# mightIO.net
KiCad netlist of a schematic drawn in EAGLE
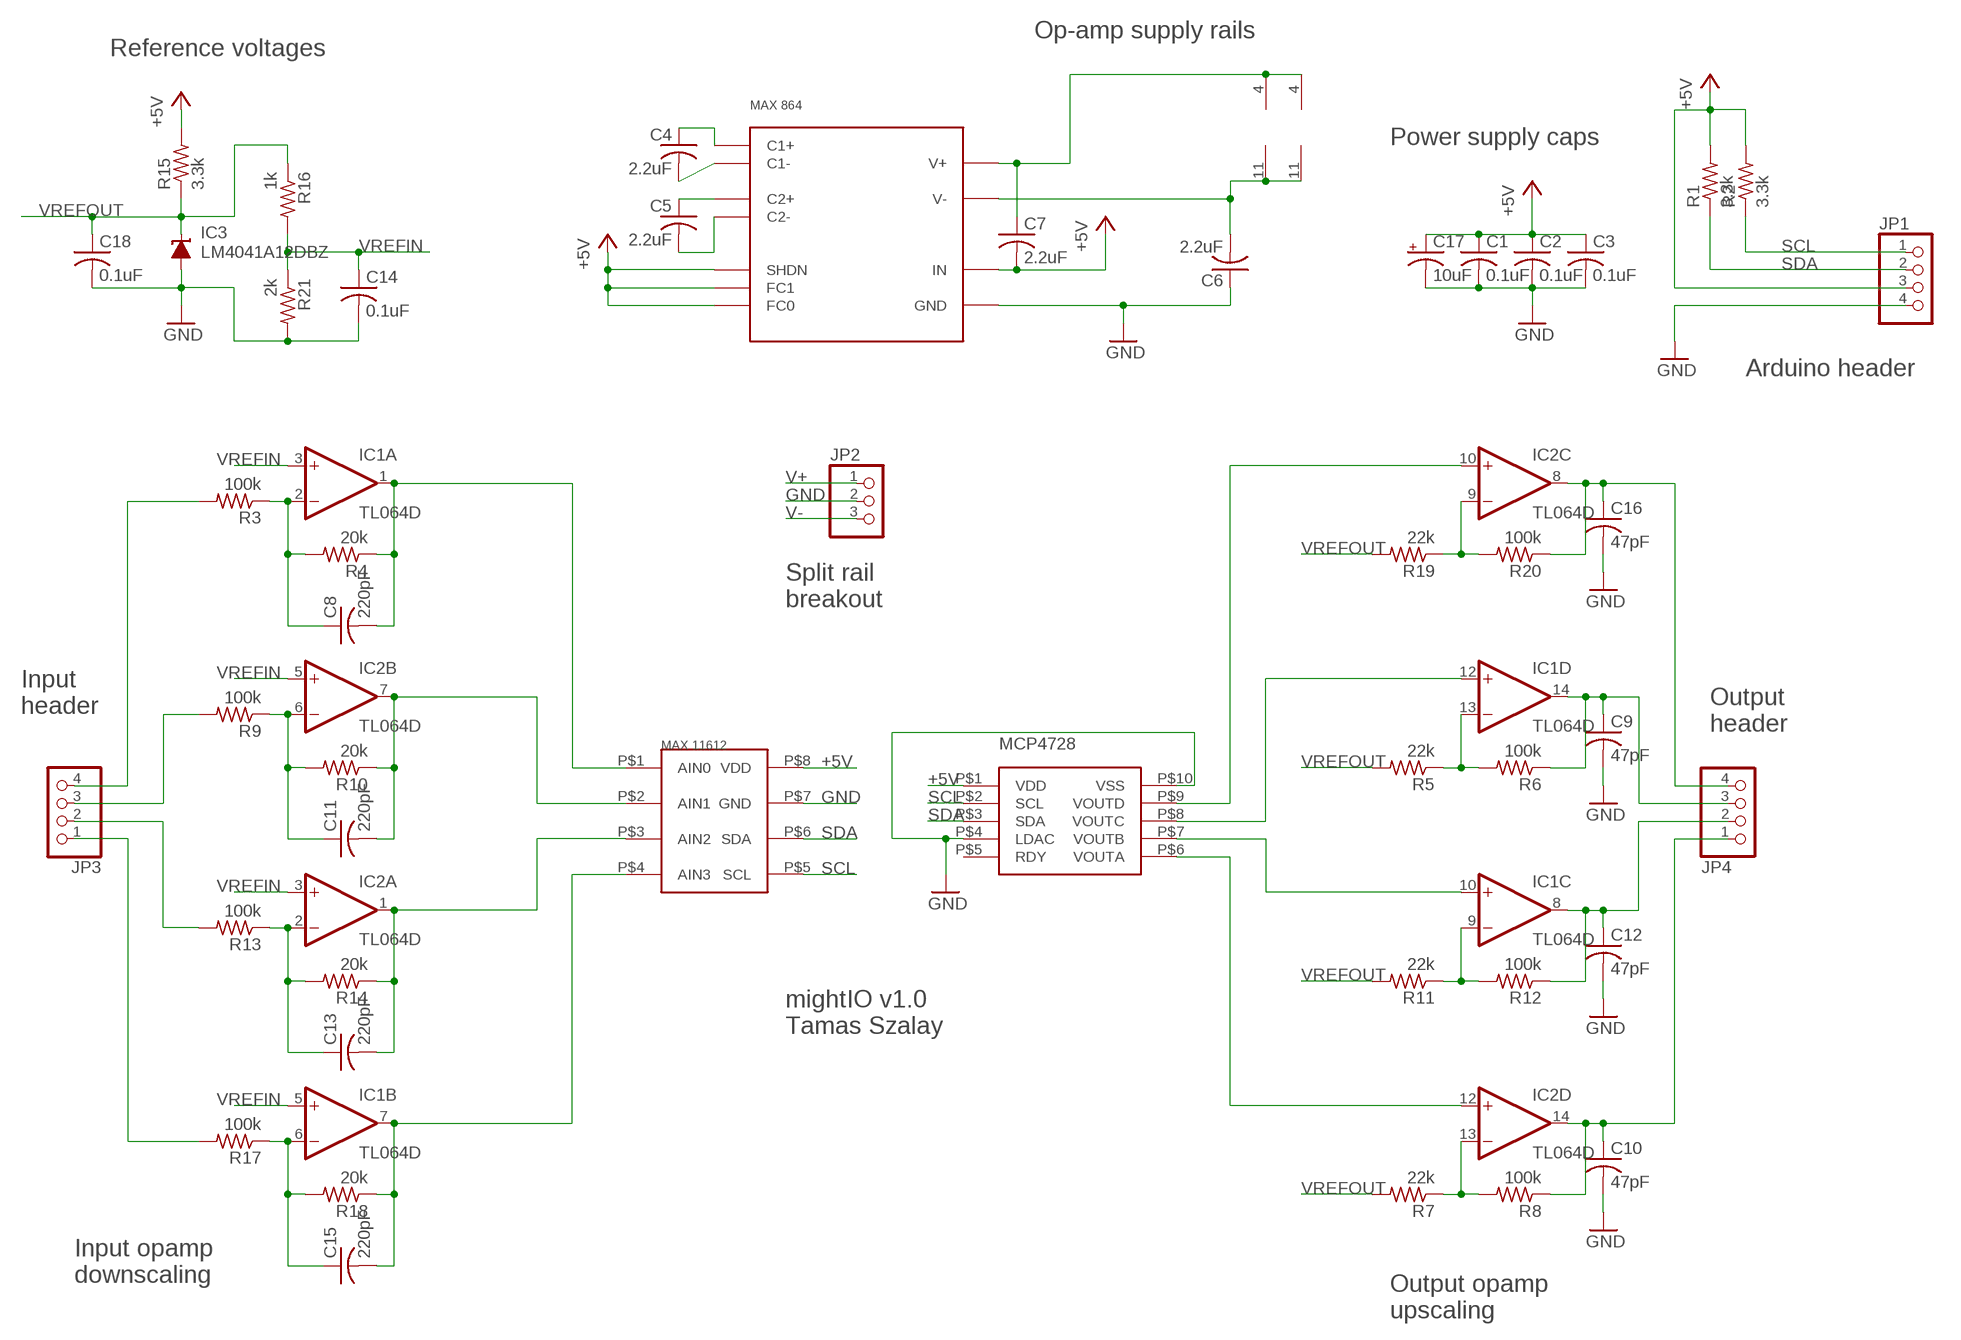
[diagram p0: schematic, sheet 1]

(export (version "E")
  (design (tool "Eeschema 10.0.6"))
  (components
    (comp (ref "C1")
      (value "0.1uF")
      (footprint "eagle-import:C0603")
      (libsource (lib "eagle-import") (part "C-USC0603"))
    )
    (comp (ref "C2")
      (value "0.1uF")
      (footprint "eagle-import:C0603")
      (libsource (lib "eagle-import") (part "C-USC0603"))
    )
    (comp (ref "C3")
      (value "0.1uF")
      (footprint "eagle-import:C0603")
      (libsource (lib "eagle-import") (part "C-USC0603"))
    )
    (comp (ref "C4")
      (value "2.2uF")
      (footprint "eagle-import:C0603")
      (libsource (lib "eagle-import") (part "C-USC0603"))
    )
    (comp (ref "C5")
      (value "2.2uF")
      (footprint "eagle-import:C0603")
      (libsource (lib "eagle-import") (part "C-USC0603"))
    )
    (comp (ref "C6")
      (value "2.2uF")
      (footprint "eagle-import:C0603")
      (libsource (lib "eagle-import") (part "C-USC0603"))
    )
    (comp (ref "C7")
      (value "2.2uF")
      (footprint "eagle-import:C0603")
      (libsource (lib "eagle-import") (part "C-USC0603"))
    )
    (comp (ref "C8")
      (value "220pF")
      (footprint "eagle-import:C0603")
      (libsource (lib "eagle-import") (part "C-USC0603"))
    )
    (comp (ref "C9")
      (value "47pF")
      (footprint "eagle-import:C0603")
      (libsource (lib "eagle-import") (part "C-USC0603"))
    )
    (comp (ref "C10")
      (value "47pF")
      (footprint "eagle-import:C0603")
      (libsource (lib "eagle-import") (part "C-USC0603"))
    )
    (comp (ref "C11")
      (value "220pF")
      (footprint "eagle-import:C0603")
      (libsource (lib "eagle-import") (part "C-USC0603"))
    )
    (comp (ref "C12")
      (value "47pF")
      (footprint "eagle-import:C0603")
      (libsource (lib "eagle-import") (part "C-USC0603"))
    )
    (comp (ref "C13")
      (value "220pF")
      (footprint "eagle-import:C0603")
      (libsource (lib "eagle-import") (part "C-USC0603"))
    )
    (comp (ref "C14")
      (value "0.1uF")
      (footprint "eagle-import:C0603")
      (libsource (lib "eagle-import") (part "C-USC0603"))
    )
    (comp (ref "C15")
      (value "220pF")
      (footprint "eagle-import:C0603")
      (libsource (lib "eagle-import") (part "C-USC0603"))
    )
    (comp (ref "C16")
      (value "47pF")
      (footprint "eagle-import:C0603")
      (libsource (lib "eagle-import") (part "C-USC0603"))
    )
    (comp (ref "C17")
      (value "10uF")
      (footprint "eagle-import:E2,5-6")
      (libsource (lib "eagle-import") (part "CPOL-USE2.5-6"))
    )
    (comp (ref "C18")
      (value "0.1uF")
      (footprint "eagle-import:C0603")
      (libsource (lib "eagle-import") (part "C-USC0603"))
    )
    (comp (ref "IC1")
      (value "TL064D")
      (footprint "eagle-import:SO14")
      (libsource (lib "eagle-import") (part "TL064D"))
    )
    (comp (ref "IC2")
      (value "TL064D")
      (footprint "eagle-import:SO14")
      (libsource (lib "eagle-import") (part "TL064D"))
    )
    (comp (ref "IC3")
      (value "LM4041A12DBZ")
      (footprint "eagle-import:DBZ_R-PDSO-G3")
      (fields (field (name "MPN") "LM4041A12IDBZR"))
      (libsource (lib "eagle-import") (part "LM4041DBZA12"))
    )
    (comp (ref "JP1")
      (value "PINHD-1X4")
      (footprint "eagle-import:1X04")
      (libsource (lib "eagle-import") (part "PINHD-1X4"))
    )
    (comp (ref "JP2")
      (value "PINHD-1X3")
      (footprint "eagle-import:1X03")
      (libsource (lib "eagle-import") (part "PINHD-1X3"))
    )
    (comp (ref "JP3")
      (value "PINHD-1X4")
      (footprint "eagle-import:1X04")
      (libsource (lib "eagle-import") (part "PINHD-1X4"))
    )
    (comp (ref "JP4")
      (value "PINHD-1X4")
      (footprint "eagle-import:1X04")
      (libsource (lib "eagle-import") (part "PINHD-1X4"))
    )
    (comp (ref "R1")
      (value "3.3k")
      (footprint "eagle-import:R0603")
      (libsource (lib "eagle-import") (part "R-US_R0603"))
    )
    (comp (ref "R2")
      (value "3.3k")
      (footprint "eagle-import:R0603")
      (libsource (lib "eagle-import") (part "R-US_R0603"))
    )
    (comp (ref "R3")
      (value "100k")
      (footprint "eagle-import:R0603")
      (libsource (lib "eagle-import") (part "R-US_R0603"))
    )
    (comp (ref "R4")
      (value "20k")
      (footprint "eagle-import:R0603")
      (libsource (lib "eagle-import") (part "R-US_R0603"))
    )
    (comp (ref "R5")
      (value "22k")
      (footprint "eagle-import:R0603")
      (libsource (lib "eagle-import") (part "R-US_R0603"))
    )
    (comp (ref "R6")
      (value "100k")
      (footprint "eagle-import:R0603")
      (libsource (lib "eagle-import") (part "R-US_R0603"))
    )
    (comp (ref "R7")
      (value "22k")
      (footprint "eagle-import:R0603")
      (libsource (lib "eagle-import") (part "R-US_R0603"))
    )
    (comp (ref "R8")
      (value "100k")
      (footprint "eagle-import:R0603")
      (libsource (lib "eagle-import") (part "R-US_R0603"))
    )
    (comp (ref "R9")
      (value "100k")
      (footprint "eagle-import:R0603")
      (libsource (lib "eagle-import") (part "R-US_R0603"))
    )
    (comp (ref "R10")
      (value "20k")
      (footprint "eagle-import:R0603")
      (libsource (lib "eagle-import") (part "R-US_R0603"))
    )
    (comp (ref "R11")
      (value "22k")
      (footprint "eagle-import:R0603")
      (libsource (lib "eagle-import") (part "R-US_R0603"))
    )
    (comp (ref "R12")
      (value "100k")
      (footprint "eagle-import:R0603")
      (libsource (lib "eagle-import") (part "R-US_R0603"))
    )
    (comp (ref "R13")
      (value "100k")
      (footprint "eagle-import:R0603")
      (libsource (lib "eagle-import") (part "R-US_R0603"))
    )
    (comp (ref "R14")
      (value "20k")
      (footprint "eagle-import:R0603")
      (libsource (lib "eagle-import") (part "R-US_R0603"))
    )
    (comp (ref "R15")
      (value "3.3k")
      (footprint "eagle-import:R0603")
      (libsource (lib "eagle-import") (part "R-US_R0603"))
    )
    (comp (ref "R16")
      (value "1k")
      (footprint "eagle-import:R0603")
      (libsource (lib "eagle-import") (part "R-US_R0603"))
    )
    (comp (ref "R17")
      (value "100k")
      (footprint "eagle-import:R0603")
      (libsource (lib "eagle-import") (part "R-US_R0603"))
    )
    (comp (ref "R18")
      (value "20k")
      (footprint "eagle-import:R0603")
      (libsource (lib "eagle-import") (part "R-US_R0603"))
    )
    (comp (ref "R19")
      (value "22k")
      (footprint "eagle-import:R0603")
      (libsource (lib "eagle-import") (part "R-US_R0603"))
    )
    (comp (ref "R20")
      (value "100k")
      (footprint "eagle-import:R0603")
      (libsource (lib "eagle-import") (part "R-US_R0603"))
    )
    (comp (ref "R21")
      (value "2k")
      (footprint "eagle-import:R0603")
      (libsource (lib "eagle-import") (part "R-US_R0603"))
    )
    (comp (ref "U$1")
      (value "MAX864")
      (footprint "eagle-import:MAX864")
      (libsource (lib "eagle-import") (part "MAX864"))
    )
    (comp (ref "U$2")
      (value "MCP4728")
      (footprint "eagle-import:MCP4728")
      (libsource (lib "eagle-import") (part "MCP4728"))
    )
    (comp (ref "U1")
      (value "MAX11612")
      (footprint "eagle-import:MAX11612")
      (libsource (lib "eagle-import") (part "MAX11612"))
    )
  )
  (nets
    (net (code "1") (name "+5V") (class "Default")
      (node (ref "C1") (pin "1") (pinfunction "1_1") (pintype "passive"))
      (node (ref "C17") (pin "+") (pinfunction "+_+") (pintype "passive"))
      (node (ref "C2") (pin "1") (pinfunction "1_1") (pintype "passive"))
      (node (ref "C3") (pin "1") (pinfunction "1_1") (pintype "passive"))
      (node (ref "C7") (pin "2") (pinfunction "2_2") (pintype "passive"))
      (node (ref "JP1") (pin "3") (pinfunction "3_3") (pintype "passive"))
      (node (ref "R1") (pin "2") (pinfunction "2_2") (pintype "passive"))
      (node (ref "R15") (pin "2") (pinfunction "2_2") (pintype "passive"))
      (node (ref "R2") (pin "2") (pinfunction "2_2") (pintype "passive"))
      (node (ref "U$1") (pin "P$12") (pinfunction "IN_P$12") (pintype "bidirectional"))
      (node (ref "U$1") (pin "P$6") (pinfunction "SHDN_P$6") (pintype "bidirectional"))
      (node (ref "U$1") (pin "P$7") (pinfunction "FC1_P$7") (pintype "bidirectional"))
      (node (ref "U$1") (pin "P$8") (pinfunction "FC0_P$8") (pintype "bidirectional"))
      (node (ref "U$2") (pin "P$1") (pinfunction "VDD_P$1") (pintype "bidirectional"))
      (node (ref "U1") (pin "P$8") (pinfunction "VDD_P$8") (pintype "bidirectional"))
    )
    (net (code "2") (name "/SCL") (class "Default")
      (node (ref "JP1") (pin "1") (pinfunction "1_1") (pintype "passive"))
      (node (ref "R2") (pin "1") (pinfunction "1_1") (pintype "passive"))
      (node (ref "U$2") (pin "P$2") (pinfunction "SCL_P$2") (pintype "bidirectional"))
      (node (ref "U1") (pin "P$5") (pinfunction "SCL_P$5") (pintype "bidirectional"))
    )
    (net (code "3") (name "/SDA") (class "Default")
      (node (ref "JP1") (pin "2") (pinfunction "2_2") (pintype "passive"))
      (node (ref "R1") (pin "1") (pinfunction "1_1") (pintype "passive"))
      (node (ref "U$2") (pin "P$3") (pinfunction "SDA_P$3") (pintype "bidirectional"))
      (node (ref "U1") (pin "P$6") (pinfunction "SDA_P$6") (pintype "bidirectional"))
    )
    (net (code "4") (name "/V+") (class "Default")
      (node (ref "C7") (pin "1") (pinfunction "1_1") (pintype "passive"))
      (node (ref "IC1") (pin "4") (pinfunction "V+_4") (pintype "power_in"))
      (node (ref "IC2") (pin "4") (pinfunction "V+_4") (pintype "power_in"))
      (node (ref "JP2") (pin "1") (pinfunction "1_1") (pintype "passive"))
      (node (ref "U$1") (pin "P$15") (pinfunction "V+_P$15") (pintype "bidirectional"))
    )
    (net (code "5") (name "/V-") (class "Default")
      (node (ref "C6") (pin "2") (pinfunction "2_2") (pintype "passive"))
      (node (ref "IC1") (pin "11") (pinfunction "V-_11") (pintype "power_in"))
      (node (ref "IC2") (pin "11") (pinfunction "V-_11") (pintype "power_in"))
      (node (ref "JP2") (pin "3") (pinfunction "3_3") (pintype "passive"))
      (node (ref "U$1") (pin "P$5") (pinfunction "V-_P$5") (pintype "bidirectional"))
    )
    (net (code "6") (name "/VREFIN") (class "Default")
      (node (ref "C14") (pin "1") (pinfunction "1_1") (pintype "passive"))
      (node (ref "IC1") (pin "3") (pinfunction "+IN_3") (pintype "input"))
      (node (ref "IC1") (pin "5") (pinfunction "+IN_5") (pintype "input"))
      (node (ref "IC2") (pin "3") (pinfunction "+IN_3") (pintype "input"))
      (node (ref "IC2") (pin "5") (pinfunction "+IN_5") (pintype "input"))
      (node (ref "R16") (pin "2") (pinfunction "2_2") (pintype "passive"))
      (node (ref "R21") (pin "1") (pinfunction "1_1") (pintype "passive"))
    )
    (net (code "7") (name "/VREFOUT") (class "Default")
      (node (ref "C18") (pin "1") (pinfunction "1_1") (pintype "passive"))
      (node (ref "IC3") (pin "1") (pinfunction "C_1") (pintype "passive"))
      (node (ref "R11") (pin "2") (pinfunction "2_2") (pintype "passive"))
      (node (ref "R15") (pin "1") (pinfunction "1_1") (pintype "passive"))
      (node (ref "R16") (pin "1") (pinfunction "1_1") (pintype "passive"))
      (node (ref "R19") (pin "2") (pinfunction "2_2") (pintype "passive"))
      (node (ref "R5") (pin "2") (pinfunction "2_2") (pintype "passive"))
      (node (ref "R7") (pin "2") (pinfunction "2_2") (pintype "passive"))
    )
    (net (code "8") (name "GND") (class "Default")
      (node (ref "C1") (pin "2") (pinfunction "2_2") (pintype "passive"))
      (node (ref "C10") (pin "2") (pinfunction "2_2") (pintype "passive"))
      (node (ref "C12") (pin "2") (pinfunction "2_2") (pintype "passive"))
      (node (ref "C14") (pin "2") (pinfunction "2_2") (pintype "passive"))
      (node (ref "C16") (pin "2") (pinfunction "2_2") (pintype "passive"))
      (node (ref "C17") (pin "-") (pinfunction "-_-") (pintype "passive"))
      (node (ref "C18") (pin "2") (pinfunction "2_2") (pintype "passive"))
      (node (ref "C2") (pin "2") (pinfunction "2_2") (pintype "passive"))
      (node (ref "C3") (pin "2") (pinfunction "2_2") (pintype "passive"))
      (node (ref "C6") (pin "1") (pinfunction "1_1") (pintype "passive"))
      (node (ref "C9") (pin "2") (pinfunction "2_2") (pintype "passive"))
      (node (ref "IC3") (pin "2") (pinfunction "A_2") (pintype "passive"))
      (node (ref "JP1") (pin "4") (pinfunction "4_4") (pintype "passive"))
      (node (ref "JP2") (pin "2") (pinfunction "2_2") (pintype "passive"))
      (node (ref "R21") (pin "2") (pinfunction "2_2") (pintype "passive"))
      (node (ref "U$1") (pin "P$11") (pinfunction "GND_P$11") (pintype "bidirectional"))
      (node (ref "U$1") (pin "P$3") (pinfunction "GND_P$3") (pintype "bidirectional"))
      (node (ref "U$2") (pin "P$10") (pinfunction "VSS_P$10") (pintype "bidirectional"))
      (node (ref "U$2") (pin "P$4") (pinfunction "LDAC_P$4") (pintype "bidirectional"))
      (node (ref "U1") (pin "P$7") (pinfunction "GND_P$7") (pintype "bidirectional"))
    )
    (net (code "9") (name "Net-(IC1A--IN)") (class "Default")
      (node (ref "C8") (pin "1") (pinfunction "1_1") (pintype "passive"))
      (node (ref "IC1") (pin "2") (pinfunction "-IN_2") (pintype "input"))
      (node (ref "R3") (pin "1") (pinfunction "1_1") (pintype "passive"))
      (node (ref "R4") (pin "2") (pinfunction "2_2") (pintype "passive"))
    )
    (net (code "10") (name "Net-(IC1A-OUT)") (class "Default")
      (node (ref "C8") (pin "2") (pinfunction "2_2") (pintype "passive"))
      (node (ref "IC1") (pin "1") (pinfunction "OUT_1") (pintype "output"))
      (node (ref "R4") (pin "1") (pinfunction "1_1") (pintype "passive"))
      (node (ref "U1") (pin "P$1") (pinfunction "AIN0_P$1") (pintype "bidirectional"))
    )
    (net (code "11") (name "Net-(IC1B--IN)") (class "Default")
      (node (ref "C15") (pin "1") (pinfunction "1_1") (pintype "passive"))
      (node (ref "IC1") (pin "6") (pinfunction "-IN_6") (pintype "input"))
      (node (ref "R17") (pin "1") (pinfunction "1_1") (pintype "passive"))
      (node (ref "R18") (pin "2") (pinfunction "2_2") (pintype "passive"))
    )
    (net (code "12") (name "Net-(IC1B-OUT)") (class "Default")
      (node (ref "C15") (pin "2") (pinfunction "2_2") (pintype "passive"))
      (node (ref "IC1") (pin "7") (pinfunction "OUT_7") (pintype "output"))
      (node (ref "R18") (pin "1") (pinfunction "1_1") (pintype "passive"))
      (node (ref "U1") (pin "P$4") (pinfunction "AIN3_P$4") (pintype "bidirectional"))
    )
    (net (code "13") (name "Net-(IC1C-+IN)") (class "Default")
      (node (ref "IC1") (pin "10") (pinfunction "+IN_10") (pintype "input"))
      (node (ref "U$2") (pin "P$7") (pinfunction "VOUTB_P$7") (pintype "bidirectional"))
    )
    (net (code "14") (name "Net-(IC1C--IN)") (class "Default")
      (node (ref "IC1") (pin "9") (pinfunction "-IN_9") (pintype "input"))
      (node (ref "R11") (pin "1") (pinfunction "1_1") (pintype "passive"))
      (node (ref "R12") (pin "2") (pinfunction "2_2") (pintype "passive"))
    )
    (net (code "15") (name "Net-(IC1C-OUT)") (class "Default")
      (node (ref "C12") (pin "1") (pinfunction "1_1") (pintype "passive"))
      (node (ref "IC1") (pin "8") (pinfunction "OUT_8") (pintype "output"))
      (node (ref "JP4") (pin "2") (pinfunction "2_2") (pintype "passive"))
      (node (ref "R12") (pin "1") (pinfunction "1_1") (pintype "passive"))
    )
    (net (code "16") (name "Net-(IC1D-+IN)") (class "Default")
      (node (ref "IC1") (pin "12") (pinfunction "+IN_12") (pintype "input"))
      (node (ref "U$2") (pin "P$8") (pinfunction "VOUTC_P$8") (pintype "bidirectional"))
    )
    (net (code "17") (name "Net-(IC1D--IN)") (class "Default")
      (node (ref "IC1") (pin "13") (pinfunction "-IN_13") (pintype "input"))
      (node (ref "R5") (pin "1") (pinfunction "1_1") (pintype "passive"))
      (node (ref "R6") (pin "2") (pinfunction "2_2") (pintype "passive"))
    )
    (net (code "18") (name "Net-(IC1D-OUT)") (class "Default")
      (node (ref "C9") (pin "1") (pinfunction "1_1") (pintype "passive"))
      (node (ref "IC1") (pin "14") (pinfunction "OUT_14") (pintype "output"))
      (node (ref "JP4") (pin "3") (pinfunction "3_3") (pintype "passive"))
      (node (ref "R6") (pin "1") (pinfunction "1_1") (pintype "passive"))
    )
    (net (code "19") (name "Net-(IC2A--IN)") (class "Default")
      (node (ref "C13") (pin "1") (pinfunction "1_1") (pintype "passive"))
      (node (ref "IC2") (pin "2") (pinfunction "-IN_2") (pintype "input"))
      (node (ref "R13") (pin "1") (pinfunction "1_1") (pintype "passive"))
      (node (ref "R14") (pin "2") (pinfunction "2_2") (pintype "passive"))
    )
    (net (code "20") (name "Net-(IC2A-OUT)") (class "Default")
      (node (ref "C13") (pin "2") (pinfunction "2_2") (pintype "passive"))
      (node (ref "IC2") (pin "1") (pinfunction "OUT_1") (pintype "output"))
      (node (ref "R14") (pin "1") (pinfunction "1_1") (pintype "passive"))
      (node (ref "U1") (pin "P$3") (pinfunction "AIN2_P$3") (pintype "bidirectional"))
    )
    (net (code "21") (name "Net-(IC2B--IN)") (class "Default")
      (node (ref "C11") (pin "1") (pinfunction "1_1") (pintype "passive"))
      (node (ref "IC2") (pin "6") (pinfunction "-IN_6") (pintype "input"))
      (node (ref "R10") (pin "2") (pinfunction "2_2") (pintype "passive"))
      (node (ref "R9") (pin "1") (pinfunction "1_1") (pintype "passive"))
    )
    (net (code "22") (name "Net-(IC2B-OUT)") (class "Default")
      (node (ref "C11") (pin "2") (pinfunction "2_2") (pintype "passive"))
      (node (ref "IC2") (pin "7") (pinfunction "OUT_7") (pintype "output"))
      (node (ref "R10") (pin "1") (pinfunction "1_1") (pintype "passive"))
      (node (ref "U1") (pin "P$2") (pinfunction "AIN1_P$2") (pintype "bidirectional"))
    )
    (net (code "23") (name "Net-(IC2C-+IN)") (class "Default")
      (node (ref "IC2") (pin "10") (pinfunction "+IN_10") (pintype "input"))
      (node (ref "U$2") (pin "P$9") (pinfunction "VOUTD_P$9") (pintype "bidirectional"))
    )
    (net (code "24") (name "Net-(IC2C--IN)") (class "Default")
      (node (ref "IC2") (pin "9") (pinfunction "-IN_9") (pintype "input"))
      (node (ref "R19") (pin "1") (pinfunction "1_1") (pintype "passive"))
      (node (ref "R20") (pin "2") (pinfunction "2_2") (pintype "passive"))
    )
    (net (code "25") (name "Net-(IC2C-OUT)") (class "Default")
      (node (ref "C16") (pin "1") (pinfunction "1_1") (pintype "passive"))
      (node (ref "IC2") (pin "8") (pinfunction "OUT_8") (pintype "output"))
      (node (ref "JP4") (pin "4") (pinfunction "4_4") (pintype "passive"))
      (node (ref "R20") (pin "1") (pinfunction "1_1") (pintype "passive"))
    )
    (net (code "26") (name "Net-(IC2D-+IN)") (class "Default")
      (node (ref "IC2") (pin "12") (pinfunction "+IN_12") (pintype "input"))
      (node (ref "U$2") (pin "P$6") (pinfunction "VOUTA_P$6") (pintype "bidirectional"))
    )
    (net (code "27") (name "Net-(IC2D--IN)") (class "Default")
      (node (ref "IC2") (pin "13") (pinfunction "-IN_13") (pintype "input"))
      (node (ref "R7") (pin "1") (pinfunction "1_1") (pintype "passive"))
      (node (ref "R8") (pin "2") (pinfunction "2_2") (pintype "passive"))
    )
    (net (code "28") (name "Net-(IC2D-OUT)") (class "Default")
      (node (ref "C10") (pin "1") (pinfunction "1_1") (pintype "passive"))
      (node (ref "IC2") (pin "14") (pinfunction "OUT_14") (pintype "output"))
      (node (ref "JP4") (pin "1") (pinfunction "1_1") (pintype "passive"))
      (node (ref "R8") (pin "1") (pinfunction "1_1") (pintype "passive"))
    )
    (net (code "29") (name "Net-(JP3-Pad1)") (class "Default")
      (node (ref "JP3") (pin "1") (pinfunction "1_1") (pintype "passive"))
      (node (ref "R17") (pin "2") (pinfunction "2_2") (pintype "passive"))
    )
    (net (code "30") (name "Net-(JP3-Pad2)") (class "Default")
      (node (ref "JP3") (pin "2") (pinfunction "2_2") (pintype "passive"))
      (node (ref "R13") (pin "2") (pinfunction "2_2") (pintype "passive"))
    )
    (net (code "31") (name "Net-(JP3-Pad3)") (class "Default")
      (node (ref "JP3") (pin "3") (pinfunction "3_3") (pintype "passive"))
      (node (ref "R9") (pin "2") (pinfunction "2_2") (pintype "passive"))
    )
    (net (code "32") (name "Net-(JP3-Pad4)") (class "Default")
      (node (ref "JP3") (pin "4") (pinfunction "4_4") (pintype "passive"))
      (node (ref "R3") (pin "2") (pinfunction "2_2") (pintype "passive"))
    )
    (net (code "33") (name "Net-(U$1-C1+)") (class "Default")
      (node (ref "C4") (pin "1") (pinfunction "1_1") (pintype "passive"))
      (node (ref "U$1") (pin "P$16") (pinfunction "C1+_P$16") (pintype "bidirectional"))
    )
    (net (code "34") (name "Net-(U$1-C1-)") (class "Default")
      (node (ref "C4") (pin "2") (pinfunction "2_2") (pintype "passive"))
      (node (ref "U$1") (pin "P$1") (pinfunction "C1-_P$1") (pintype "bidirectional"))
    )
    (net (code "35") (name "Net-(U$1-C2+)") (class "Default")
      (node (ref "C5") (pin "1") (pinfunction "1_1") (pintype "passive"))
      (node (ref "U$1") (pin "P$2") (pinfunction "C2+_P$2") (pintype "bidirectional"))
    )
    (net (code "36") (name "Net-(U$1-C2-)") (class "Default")
      (node (ref "C5") (pin "2") (pinfunction "2_2") (pintype "passive"))
      (node (ref "U$1") (pin "P$4") (pinfunction "C2-_P$4") (pintype "bidirectional"))
    )
    (net (code "37") (name "unconnected-(U$2-RDY-PadP$5)") (class "Default")
      (node (ref "U$2") (pin "P$5") (pinfunction "RDY_P$5") (pintype "bidirectional"))
    )
  )
)
